# Carte_du_Panier.net
KiCad netlist of a schematic drawn in EAGLE
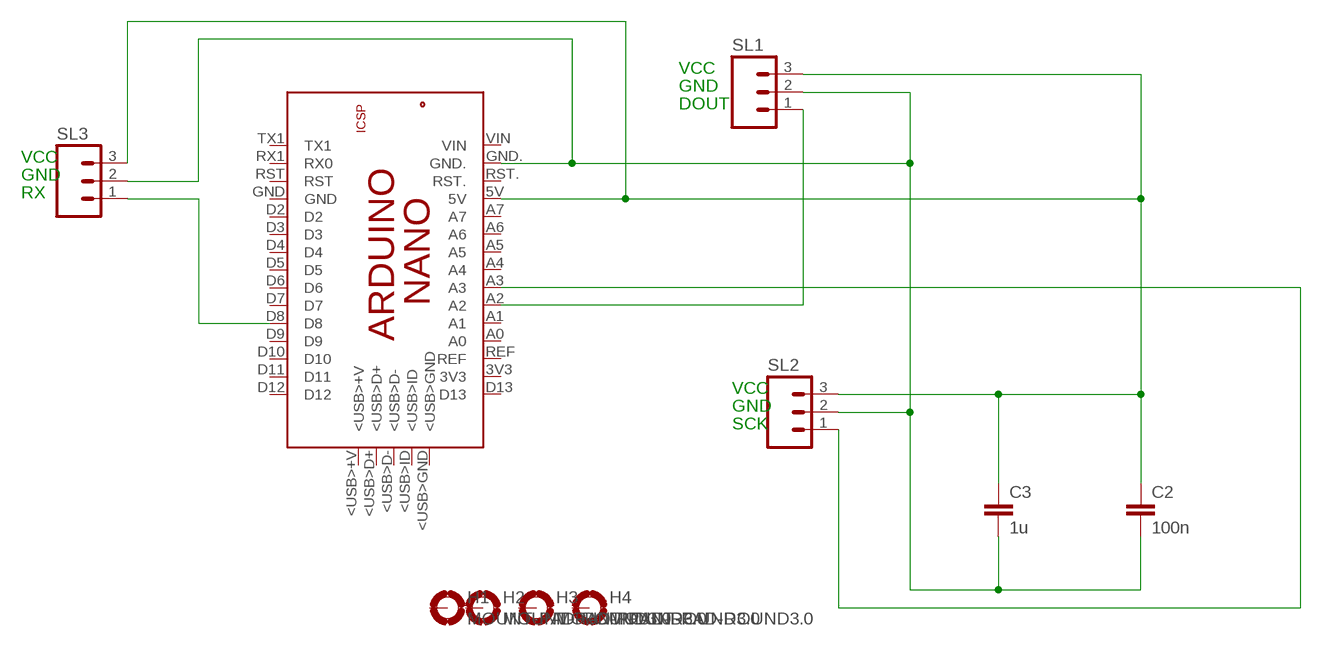
[diagram p0: schematic, sheet 1]

(export (version "E")
  (design (tool "Eeschema 10.0.6"))
  (components
    (comp (ref "C2")
      (value "100n")
      (footprint "eagle-import:C025-024X044")
      (libsource (lib "eagle-import") (part "C-EU025-024X044"))
    )
    (comp (ref "C3")
      (value "1u")
      (footprint "eagle-import:C025-024X044")
      (libsource (lib "eagle-import") (part "C-EU025-024X044"))
    )
    (comp (ref "H1")
      (value "MOUNT-PAD-ROUND3.0")
      (footprint "eagle-import:3,0-PAD")
      (libsource (lib "eagle-import") (part "MOUNT-PAD-ROUND3.0"))
    )
    (comp (ref "H2")
      (value "MOUNT-PAD-ROUND3.0")
      (footprint "eagle-import:3,0-PAD")
      (libsource (lib "eagle-import") (part "MOUNT-PAD-ROUND3.0"))
    )
    (comp (ref "H3")
      (value "MOUNT-PAD-ROUND3.0")
      (footprint "eagle-import:3,0-PAD")
      (libsource (lib "eagle-import") (part "MOUNT-PAD-ROUND3.0"))
    )
    (comp (ref "H4")
      (value "MOUNT-PAD-ROUND3.0")
      (footprint "eagle-import:3,0-PAD")
      (libsource (lib "eagle-import") (part "MOUNT-PAD-ROUND3.0"))
    )
    (comp (ref "PCB1")
      (value "ARDUINO_NANO")
      (footprint "eagle-import:ARDUINO_NANO")
      (libsource (lib "eagle-import") (part "ARDUINO_NANO"))
    )
    (comp (ref "SL1")
      (value "M03")
      (footprint "eagle-import:03P")
      (libsource (lib "eagle-import") (part "M03"))
    )
    (comp (ref "SL2")
      (value "M03")
      (footprint "eagle-import:03P")
      (libsource (lib "eagle-import") (part "M03"))
    )
    (comp (ref "SL3")
      (value "M03")
      (footprint "eagle-import:03P")
      (libsource (lib "eagle-import") (part "M03"))
    )
  )
  (nets
    (net (code "1") (name "Net-(C2-Pad1)") (class "Default")
      (node (ref "C2") (pin "1") (pinfunction "1_1") (pintype "passive"))
      (node (ref "C3") (pin "1") (pinfunction "1_1") (pintype "passive"))
      (node (ref "PCB1") (pin "5V") (pinfunction "5V_5V") (pintype "bidirectional"))
      (node (ref "SL1") (pin "3") (pinfunction "3_3") (pintype "passive"))
      (node (ref "SL2") (pin "3") (pinfunction "3_3") (pintype "passive"))
      (node (ref "SL3") (pin "3") (pinfunction "3_3") (pintype "passive"))
    )
    (net (code "2") (name "Net-(C2-Pad2)") (class "Default")
      (node (ref "C2") (pin "2") (pinfunction "2_2") (pintype "passive"))
      (node (ref "C3") (pin "2") (pinfunction "2_2") (pintype "passive"))
      (node (ref "PCB1") (pin "GND.") (pinfunction "GND._GND.") (pintype "bidirectional"))
      (node (ref "SL1") (pin "2") (pinfunction "2_2") (pintype "passive"))
      (node (ref "SL2") (pin "2") (pinfunction "2_2") (pintype "passive"))
      (node (ref "SL3") (pin "2") (pinfunction "2_2") (pintype "passive"))
    )
    (net (code "3") (name "Net-(PCB1-PadA2)") (class "Default")
      (node (ref "PCB1") (pin "A2") (pinfunction "A2_A2") (pintype "bidirectional"))
      (node (ref "SL1") (pin "1") (pinfunction "1_1") (pintype "passive"))
    )
    (net (code "4") (name "Net-(PCB1-PadA3)") (class "Default")
      (node (ref "PCB1") (pin "A3") (pinfunction "A3_A3") (pintype "bidirectional"))
      (node (ref "SL2") (pin "1") (pinfunction "1_1") (pintype "passive"))
    )
    (net (code "5") (name "Net-(PCB1-PadD8)") (class "Default")
      (node (ref "PCB1") (pin "D8") (pinfunction "D8_D8") (pintype "bidirectional"))
      (node (ref "SL3") (pin "1") (pinfunction "1_1") (pintype "passive"))
    )
    (net (code "6") (name "unconnected-(H1-MOUNT-PadB3,0)") (class "Default")
      (node (ref "H1") (pin "B3,0") (pinfunction "MOUNT_B3,0") (pintype "passive"))
    )
    (net (code "7") (name "unconnected-(H2-MOUNT-PadB3,0)") (class "Default")
      (node (ref "H2") (pin "B3,0") (pinfunction "MOUNT_B3,0") (pintype "passive"))
    )
    (net (code "8") (name "unconnected-(H3-MOUNT-PadB3,0)") (class "Default")
      (node (ref "H3") (pin "B3,0") (pinfunction "MOUNT_B3,0") (pintype "passive"))
    )
    (net (code "9") (name "unconnected-(H4-MOUNT-PadB3,0)") (class "Default")
      (node (ref "H4") (pin "B3,0") (pinfunction "MOUNT_B3,0") (pintype "passive"))
    )
    (net (code "10") (name "unconnected-(PCB1-Pad3V3)") (class "Default")
      (node (ref "PCB1") (pin "3V3") (pinfunction "3V3_3V3") (pintype "bidirectional"))
    )
    (net (code "11") (name "unconnected-(PCB1-Pad5V.)") (class "Default")
      (node (ref "PCB1") (pin "5V.") (pinfunction "5V._5V.") (pintype "bidirectional"))
    )
    (net (code "12") (name "unconnected-(PCB1-Pad<USB>+V)") (class "Default")
      (node (ref "PCB1") (pin "<USB>+V") (pinfunction "<USB>+V_<USB>+V") (pintype "bidirectional"))
    )
    (net (code "13") (name "unconnected-(PCB1-Pad<USB>D+)") (class "Default")
      (node (ref "PCB1") (pin "<USB>D+") (pinfunction "<USB>D+_<USB>D+") (pintype "bidirectional"))
    )
    (net (code "14") (name "unconnected-(PCB1-Pad<USB>D-)") (class "Default")
      (node (ref "PCB1") (pin "<USB>D-") (pinfunction "<USB>D-_<USB>D-") (pintype "bidirectional"))
    )
    (net (code "15") (name "unconnected-(PCB1-Pad<USB>GND)") (class "Default")
      (node (ref "PCB1") (pin "<USB>GND") (pinfunction "<USB>GND_<USB>GND") (pintype "bidirectional"))
    )
    (net (code "16") (name "unconnected-(PCB1-Pad<USB>ID)") (class "Default")
      (node (ref "PCB1") (pin "<USB>ID") (pinfunction "<USB>ID_<USB>ID") (pintype "bidirectional"))
    )
    (net (code "17") (name "unconnected-(PCB1-PadA0)") (class "Default")
      (node (ref "PCB1") (pin "A0") (pinfunction "A0_A0") (pintype "bidirectional"))
    )
    (net (code "18") (name "unconnected-(PCB1-PadA1)") (class "Default")
      (node (ref "PCB1") (pin "A1") (pinfunction "A1_A1") (pintype "bidirectional"))
    )
    (net (code "19") (name "unconnected-(PCB1-PadA4)") (class "Default")
      (node (ref "PCB1") (pin "A4") (pinfunction "A4_A4") (pintype "bidirectional"))
    )
    (net (code "20") (name "unconnected-(PCB1-PadA5)") (class "Default")
      (node (ref "PCB1") (pin "A5") (pinfunction "A5_A5") (pintype "bidirectional"))
    )
    (net (code "21") (name "unconnected-(PCB1-PadA6)") (class "Default")
      (node (ref "PCB1") (pin "A6") (pinfunction "A6_A6") (pintype "bidirectional"))
    )
    (net (code "22") (name "unconnected-(PCB1-PadA7)") (class "Default")
      (node (ref "PCB1") (pin "A7") (pinfunction "A7_A7") (pintype "bidirectional"))
    )
    (net (code "23") (name "unconnected-(PCB1-PadD2)") (class "Default")
      (node (ref "PCB1") (pin "D2") (pinfunction "D2_D2") (pintype "bidirectional"))
    )
    (net (code "24") (name "unconnected-(PCB1-PadD3)") (class "Default")
      (node (ref "PCB1") (pin "D3") (pinfunction "D3_D3") (pintype "bidirectional"))
    )
    (net (code "25") (name "unconnected-(PCB1-PadD4)") (class "Default")
      (node (ref "PCB1") (pin "D4") (pinfunction "D4_D4") (pintype "bidirectional"))
    )
    (net (code "26") (name "unconnected-(PCB1-PadD5)") (class "Default")
      (node (ref "PCB1") (pin "D5") (pinfunction "D5_D5") (pintype "bidirectional"))
    )
    (net (code "27") (name "unconnected-(PCB1-PadD6)") (class "Default")
      (node (ref "PCB1") (pin "D6") (pinfunction "D6_D6") (pintype "bidirectional"))
    )
    (net (code "28") (name "unconnected-(PCB1-PadD7)") (class "Default")
      (node (ref "PCB1") (pin "D7") (pinfunction "D7_D7") (pintype "bidirectional"))
    )
    (net (code "29") (name "unconnected-(PCB1-PadD9)") (class "Default")
      (node (ref "PCB1") (pin "D9") (pinfunction "D9_D9") (pintype "bidirectional"))
    )
    (net (code "30") (name "unconnected-(PCB1-PadD10)") (class "Default")
      (node (ref "PCB1") (pin "D10") (pinfunction "D10_D10") (pintype "bidirectional"))
    )
    (net (code "31") (name "unconnected-(PCB1-PadD11)") (class "Default")
      (node (ref "PCB1") (pin "D11") (pinfunction "D11_D11") (pintype "bidirectional"))
    )
    (net (code "32") (name "unconnected-(PCB1-PadD12)") (class "Default")
      (node (ref "PCB1") (pin "D12") (pinfunction "D12_D12") (pintype "bidirectional"))
    )
    (net (code "33") (name "unconnected-(PCB1-PadD13)") (class "Default")
      (node (ref "PCB1") (pin "D13") (pinfunction "D13_D13") (pintype "bidirectional"))
    )
    (net (code "34") (name "unconnected-(PCB1-PadGND)") (class "Default")
      (node (ref "PCB1") (pin "GND") (pinfunction "GND_GND") (pintype "bidirectional"))
    )
    (net (code "35") (name "unconnected-(PCB1-PadGND_)") (class "Default")
      (node (ref "PCB1") (pin "GND_") (pinfunction "GND__GND_") (pintype "bidirectional"))
    )
    (net (code "36") (name "unconnected-(PCB1-PadMISO)") (class "Default")
      (node (ref "PCB1") (pin "MISO") (pinfunction "MISO_MISO") (pintype "bidirectional"))
    )
    (net (code "37") (name "unconnected-(PCB1-PadMOSI)") (class "Default")
      (node (ref "PCB1") (pin "MOSI") (pinfunction "MOSI_MOSI") (pintype "bidirectional"))
    )
    (net (code "38") (name "unconnected-(PCB1-PadREF)") (class "Default")
      (node (ref "PCB1") (pin "REF") (pinfunction "REF_REF") (pintype "bidirectional"))
    )
    (net (code "39") (name "unconnected-(PCB1-PadRESET..)") (class "Default")
      (node (ref "PCB1") (pin "RESET..") (pinfunction "RESET.._RESET..") (pintype "bidirectional"))
    )
    (net (code "40") (name "unconnected-(PCB1-PadRST)") (class "Default")
      (node (ref "PCB1") (pin "RST") (pinfunction "RST_RST") (pintype "bidirectional"))
    )
    (net (code "41") (name "unconnected-(PCB1-PadRST.)") (class "Default")
      (node (ref "PCB1") (pin "RST.") (pinfunction "RST._RST.") (pintype "bidirectional"))
    )
    (net (code "42") (name "unconnected-(PCB1-PadSCK)") (class "Default")
      (node (ref "PCB1") (pin "SCK") (pinfunction "SCK_SCK") (pintype "bidirectional"))
    )
    (net (code "43") (name "unconnected-(PCB1-PadTX1)") (class "Default")
      (node (ref "PCB1") (pin "TX1") (pinfunction "TX1_TX1") (pintype "bidirectional"))
    )
    (net (code "44") (name "unconnected-(PCB1-PadVIN)") (class "Default")
      (node (ref "PCB1") (pin "VIN") (pinfunction "VIN_VIN") (pintype "bidirectional"))
    )
    (net (code "45") (name "unconnected-(PCB1-RX0-PadRX1)") (class "Default")
      (node (ref "PCB1") (pin "RX1") (pinfunction "RX0_RX1") (pintype "bidirectional"))
    )
  )
)
